# LionIRVT-Power.net
KiCad netlist of a schematic drawn in Altium Designer
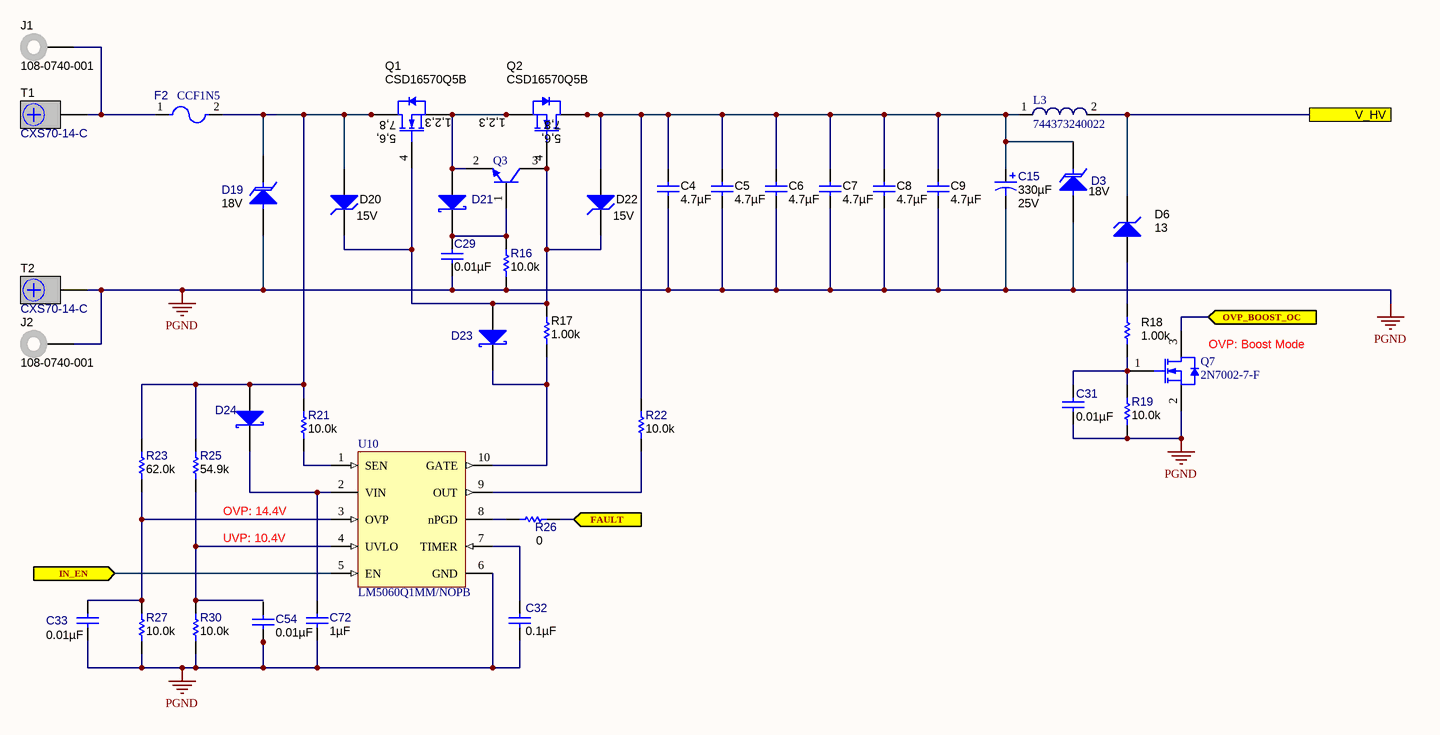
[diagram p0: LionIRVT-Power.SchDoc]

(export (version "E")
  (design (tool "Eeschema 10.0.6"))
  (components
    (comp (ref "C4")
      (value "C5750X7R2A475M230KA")
      (footprint "2220_280")
      (description "CAP, CERM, 4.7 µF, 100 V, +/- 20%, X7R, 2220")
      (fields
        (field (name "VALUEDISPLAYED") "4.7µF")
        (field (name "MANUFACTURER") "TDK")
        (field (name "PUBLISHER") "Texas Instruments")
      )
      (libsource (lib "Capacitor_Ceramic") (part "C5750X7R2A475M230KA"))
    )
    (comp (ref "C5")
      (value "C5750X7R2A475M230KA")
      (footprint "2220_280")
      (description "CAP, CERM, 4.7 µF, 100 V, +/- 20%, X7R, 2220")
      (fields
        (field (name "VALUEDISPLAYED") "4.7µF")
        (field (name "MANUFACTURER") "TDK")
        (field (name "PUBLISHER") "Texas Instruments")
      )
      (libsource (lib "Capacitor_Ceramic") (part "C5750X7R2A475M230KA"))
    )
    (comp (ref "C6")
      (value "C5750X7R2A475M230KA")
      (footprint "2220_280")
      (description "CAP, CERM, 4.7 µF, 100 V, +/- 20%, X7R, 2220")
      (fields
        (field (name "VALUEDISPLAYED") "4.7µF")
        (field (name "MANUFACTURER") "TDK")
        (field (name "PUBLISHER") "Texas Instruments")
      )
      (libsource (lib "Capacitor_Ceramic") (part "C5750X7R2A475M230KA"))
    )
    (comp (ref "C7")
      (value "C5750X7R2A475M230KA")
      (footprint "2220_280")
      (description "CAP, CERM, 4.7 µF, 100 V, +/- 20%, X7R, 2220")
      (fields
        (field (name "VALUEDISPLAYED") "4.7µF")
        (field (name "MANUFACTURER") "TDK")
        (field (name "PUBLISHER") "Texas Instruments")
      )
      (libsource (lib "Capacitor_Ceramic") (part "C5750X7R2A475M230KA"))
    )
    (comp (ref "C8")
      (value "C5750X7R2A475M230KA")
      (footprint "2220_280")
      (description "CAP, CERM, 4.7 µF, 100 V, +/- 20%, X7R, 2220")
      (fields
        (field (name "VALUEDISPLAYED") "4.7µF")
        (field (name "MANUFACTURER") "TDK")
        (field (name "PUBLISHER") "Texas Instruments")
      )
      (libsource (lib "Capacitor_Ceramic") (part "C5750X7R2A475M230KA"))
    )
    (comp (ref "C9")
      (value "C5750X7R2A475M230KA")
      (footprint "2220_280")
      (description "CAP, CERM, 4.7 µF, 100 V, +/- 20%, X7R, 2220")
      (fields
        (field (name "VALUEDISPLAYED") "4.7µF")
        (field (name "MANUFACTURER") "TDK")
        (field (name "PUBLISHER") "Texas Instruments")
      )
      (libsource (lib "Capacitor_Ceramic") (part "C5750X7R2A475M230KA"))
    )
    (comp (ref "C15")
      (value "25SVPF330M")
      (footprint "CAPSMT_62_F12")
      (fields
        (field (name "VALUEDISPLAYED") "330µF")
        (field (name "MANUFACTURER") "Panasonic")
        (field (name "VALUE2") "25V")
        (field (name "PUBLISHER") "Texas Instruments")
      )
      (libsource (lib "PMP40182") (part "25SVPF330M"))
    )
    (comp (ref "C29")
      (value "GRM1885C1H103JA01D")
      (footprint "0603C")
      (description "CAP, CERM, 0.01 µF, 50 V, +/- 5%, C0G/NP0, 0603")
      (fields
        (field (name "VALUEDISPLAYED") "0.01µF")
        (field (name "MANUFACTURER") "MuRata")
        (field (name "PUBLISHER") "Texas Instruments")
      )
      (libsource (lib "Capacitor_Ceramic") (part "GRM1885C1H103JA01D"))
    )
    (comp (ref "C31")
      (value "GRM1885C1H103JA01D")
      (footprint "0603C")
      (description "CAP, CERM, 0.01 µF, 50 V, +/- 5%, C0G/NP0, 0603")
      (fields
        (field (name "VALUEDISPLAYED") "0.01µF")
        (field (name "MANUFACTURER") "MuRata")
        (field (name "PUBLISHER") "Texas Instruments")
      )
      (libsource (lib "Capacitor_Ceramic") (part "GRM1885C1H103JA01D"))
    )
    (comp (ref "C32")
      (value "C0603C104J3RACTU")
      (footprint "0603C")
      (description "CAP, CERM, 0.1 µF, 25 V, +/- 5%, X7R, 0603")
      (fields
        (field (name "VALUEDISPLAYED") "0.1µF")
        (field (name "MANUFACTURER") "Kemet")
        (field (name "PUBLISHER") "Texas Instruments")
      )
      (libsource (lib "Capacitor_Ceramic") (part "C0603C104J3RACTU"))
    )
    (comp (ref "C33")
      (value "GRM1885C1H103JA01D")
      (footprint "0603C")
      (description "CAP, CERM, 0.01 µF, 50 V, +/- 5%, C0G/NP0, 0603")
      (fields
        (field (name "VALUEDISPLAYED") "0.01µF")
        (field (name "MANUFACTURER") "MuRata")
        (field (name "PUBLISHER") "Texas Instruments")
      )
      (libsource (lib "Capacitor_Ceramic") (part "GRM1885C1H103JA01D"))
    )
    (comp (ref "C54")
      (value "GRM1885C1H103JA01D")
      (footprint "0603C")
      (description "CAP, CERM, 0.01 µF, 50 V, +/- 5%, C0G/NP0, 0603")
      (fields
        (field (name "VALUEDISPLAYED") "0.01µF")
        (field (name "MANUFACTURER") "MuRata")
        (field (name "PUBLISHER") "Texas Instruments")
      )
      (libsource (lib "Capacitor_Ceramic") (part "GRM1885C1H103JA01D"))
    )
    (comp (ref "C72")
      (value "C0603C105K3RACTU")
      (footprint "0603C")
      (description "CAP, CERM, 1 µF, 25 V, +/- 10%, X7R, 0603")
      (fields
        (field (name "VALUEDISPLAYED") "1µF")
        (field (name "MANUFACTURER") "Kemet")
        (field (name "PUBLISHER") "Texas Instruments")
      )
      (libsource (lib "Capacitor_Ceramic") (part "C0603C105K3RACTU"))
    )
    (comp (ref "D3")
      (value "18V")
      (footprint "SMA")
      (description "Diode, TVS, Uni, 18 V, 29.2 Vc, SMA")
      (fields
        (field (name "PARTNUMBER") "SMAJ18A")
        (field (name "MANUFACTURER") "Littelfuse")
        (field (name "PUBLISHER") "Texas Instruments")
      )
      (libsource (lib "PMP40182") (part "SMAJ18A"))
    )
    (comp (ref "D6")
      (value "13")
      (footprint "sod-323")
      (description "Diode, Zener, 13V, 200mW, SOD-323")
      (fields
        (field (name "PARTNUMBER") "MMSZ5243BS-7-F")
        (field (name "MANUFACTURER") "Diodes Inc.")
        (field (name "PUBLISHER") "Texas Instruments")
      )
      (libsource (lib "PWR578A") (part "MMSZ5243BS-7-F"))
    )
    (comp (ref "D19")
      (value "18V")
      (footprint "SMA")
      (description "Diode, TVS, Uni, 18 V, 29.2 Vc, SMA")
      (fields
        (field (name "PARTNUMBER") "SMAJ18A")
        (field (name "MANUFACTURER") "Littelfuse")
        (field (name "PUBLISHER") "Texas Instruments")
      )
      (libsource (lib "ZenerDiodes") (part "SMAJ18A"))
    )
    (comp (ref "D20")
      (value "15V")
      (footprint "sod-323")
      (description "Diode, Zener, 15 V, 200 mW, SOD-323")
      (fields
        (field (name "PARTNUMBER") "MMSZ5245BS-7-F")
        (field (name "MANUFACTURER") "Diodes Inc.")
        (field (name "SYMBOLCREATOR") "a0412235")
        (field (name "PUBLISHER") "Texas Instruments")
      )
      (libsource (lib "ZenerDiodes") (part "MMSZ5245BS-7-F"))
    )
    (comp (ref "D21")
      (value "NSR0240V2T1G")
      (footprint "SOD-523")
      (description "Diode, Schottky, 40V, 0.25A, SOD-523")
      (fields (field (name "MANUFACTURER") "ON Semiconductor") (field (name "PUBLISHER") "Texas Instruments"))
      (libsource (lib "Diode") (part "NSR0240V2T1G"))
    )
    (comp (ref "D22")
      (value "15V")
      (footprint "sod-323")
      (description "Diode, Zener, 15 V, 200 mW, SOD-323")
      (fields
        (field (name "PARTNUMBER") "MMSZ5245BS-7-F")
        (field (name "MANUFACTURER") "Diodes Inc.")
        (field (name "SYMBOLCREATOR") "a0412235")
        (field (name "PUBLISHER") "Texas Instruments")
      )
      (libsource (lib "ZenerDiodes") (part "MMSZ5245BS-7-F"))
    )
    (comp (ref "D23")
      (value "NSR0240V2T1G")
      (footprint "SOD-523")
      (description "Diode, Schottky, 40V, 0.25A, SOD-523")
      (fields (field (name "MANUFACTURER") "ON Semiconductor") (field (name "PUBLISHER") "Texas Instruments"))
      (libsource (lib "Diode") (part "NSR0240V2T1G"))
    )
    (comp (ref "D24")
      (value "NSR0240V2T1G")
      (footprint "SOD-523")
      (description "Diode, Schottky, 40V, 0.25A, SOD-523")
      (fields (field (name "MANUFACTURER") "ON Semiconductor") (field (name "PUBLISHER") "Texas Instruments"))
      (libsource (lib "Diode") (part "NSR0240V2T1G"))
    )
    (comp (ref "F2")
      (value "CCF1N5")
      (footprint "FUSE_CCF")
      (description "Fuse, Fast Acting, 50VDC, 20A")
      (fields (field (name "MANUFACTURER") "Koanet"))
      (libsource (lib "PADSlegacy_Passive") (part "FUSE_CCF1N_SERIES"))
    )
    (comp (ref "J1")
      (value "108-0740-001")
      (footprint "Johnson_108-0740-001")
      (description "Standard Banana Jack, Uninsulated, 15A")
      (fields
        (field (name "MANUFACTURER") "Emerson Network Power")
        (field (name "SYMBOLCREATOR") "a0412235")
        (field (name "PUBLISHER") "Texas Instruments")
      )
      (libsource (lib "Connectors_Other") (part "108-0740-001"))
    )
    (comp (ref "J2")
      (value "108-0740-001")
      (footprint "Johnson_108-0740-001")
      (description "Standard Banana Jack, Uninsulated, 15A")
      (fields
        (field (name "MANUFACTURER") "Emerson Network Power")
        (field (name "SYMBOLCREATOR") "a0412235")
        (field (name "PUBLISHER") "Texas Instruments")
      )
      (libsource (lib "Connectors_Other") (part "108-0740-001"))
    )
    (comp (ref "L3")
      (value "744373240022")
      (footprint "WE-LHMI 4020")
      (description "SMD Power Inductor WE-LHMI, L=0.22 µH")
      (fields (field (name "MANUFACTURER") "Wuerth Elektronik"))
      (libsource (lib "Altium Content Vault") (part "WE-IND-INDUCTOR-2"))
    )
    (comp (ref "Q1")
      (value "CSD16570Q5B")
      (footprint "DNK8")
      (description "25V, N ch NexFET MOSFET™, single SON5x6, 0.82mOhm")
      (fields
        (field (name "MANUFACTURER") "Texas Instruments")
        (field (name "MANUFACTURER PART NUMBER") "CSD16570Q5BT")
      )
      (libsource (lib "PWR578A") (part "CSD16570Q5B"))
    )
    (comp (ref "Q2")
      (value "CSD16570Q5B")
      (footprint "DNK8")
      (description "25V, N ch NexFET MOSFET™, single SON5x6, 0.82mOhm")
      (fields
        (field (name "MANUFACTURER") "Texas Instruments")
        (field (name "MANUFACTURER PART NUMBER") "CSD16570Q5BT")
      )
      (libsource (lib "PWR578A") (part "CSD16570Q5B"))
    )
    (comp (ref "Q3")
      (value "MMBT2222ALT1G")
      (footprint "ONSC-SOT-23-3-318-08_V")
      (description "General Purpose Transistor, NPN Silicon, 3-Pin SOT-23, Pb-Free, Tape and Reel")
      (fields (field (name "MANUFACTURER") "On Semiconductor"))
      (libsource (lib "Altium Content Vault") (part "ONSC-NPN-B1E2C3-3"))
    )
    (comp (ref "Q7")
      (value "2N7002-7-F")
      (footprint "DIOD-SOT23-3_V")
      (fields (field (name "MANUFACTURER") "DiodesIncorporated"))
      (libsource (lib "Altium Content Vault") (part "NEMOS-GSD-3"))
    )
    (comp (ref "R16")
      (value "RC0603FR-0710KL")
      (footprint "0603R")
      (description "RES, 10.0 k, 1%, 0.1 W, 0603")
      (fields
        (field (name "VALUEDISPLAYED") "10.0k")
        (field (name "MANUFACTURER") "Yageo America")
        (field (name "PUBLISHER") "Texas Instruments")
      )
      (libsource (lib "Resistor_0603") (part "RC0603FR-0710KL"))
    )
    (comp (ref "R17")
      (value "Resistor")
      (footprint "0603R")
      (description "RES, 1.00 k, 1%, 0.1 W, AEC-Q200 Grade 0, 0603")
      (fields
        (field (name "PARTNUMBER") "CRCW06031K00FKEA")
        (field (name "MANUFACTURER") "Vishay-Dale")
        (field (name "VALUEDISPLAYED") "1.00k")
      )
      (libsource (lib "PMP40182") (part "CMP-0022109-5"))
    )
    (comp (ref "R18")
      (value "Resistor")
      (footprint "0603R")
      (description "RES, 1.00 k, 1%, 0.1 W, AEC-Q200 Grade 0, 0603")
      (fields
        (field (name "PARTNUMBER") "CRCW06031K00FKEA")
        (field (name "MANUFACTURER") "Vishay-Dale")
        (field (name "VALUEDISPLAYED") "1.00k")
      )
      (libsource (lib "PMP40182") (part "CMP-0022109-5"))
    )
    (comp (ref "R19")
      (value "RC0603FR-0710KL")
      (footprint "0603R")
      (description "RES, 10.0 k, 1%, 0.1 W, 0603")
      (fields
        (field (name "VALUEDISPLAYED") "10.0k")
        (field (name "MANUFACTURER") "Yageo America")
        (field (name "PUBLISHER") "Texas Instruments")
      )
      (libsource (lib "Resistor_0603") (part "RC0603FR-0710KL"))
    )
    (comp (ref "R21")
      (value "RC0603FR-0710KL")
      (footprint "0603R")
      (description "RES, 10.0 k, 1%, 0.1 W, 0603")
      (fields
        (field (name "VALUEDISPLAYED") "10.0k")
        (field (name "MANUFACTURER") "Yageo America")
        (field (name "PUBLISHER") "Texas Instruments")
      )
      (libsource (lib "Resistor_0603") (part "RC0603FR-0710KL"))
    )
    (comp (ref "R22")
      (value "RC0603FR-0710KL")
      (footprint "0603R")
      (description "RES, 10.0 k, 1%, 0.1 W, 0603")
      (fields
        (field (name "VALUEDISPLAYED") "10.0k")
        (field (name "MANUFACTURER") "Yageo America")
        (field (name "PUBLISHER") "Texas Instruments")
      )
      (libsource (lib "Resistor_0603") (part "RC0603FR-0710KL"))
    )
    (comp (ref "R23")
      (value "RC0603FR-0762KL")
      (footprint "0603R")
      (description "RES, 62.0 k, 1%, 0.1 W, 0603")
      (fields
        (field (name "VALUEDISPLAYED") "62.0k")
        (field (name "MANUFACTURER") "Yageo America")
        (field (name "PUBLISHER") "Texas Instruments")
      )
      (libsource (lib "Resistor_0603") (part "RC0603FR-0762KL"))
    )
    (comp (ref "R25")
      (value "RC0603FR-0754K9L")
      (footprint "0603R")
      (description "RES, 54.9 k, 1%, 0.1 W, 0603")
      (fields
        (field (name "VALUEDISPLAYED") "54.9k")
        (field (name "MANUFACTURER") "Yageo America")
        (field (name "PUBLISHER") "Texas Instruments")
      )
      (libsource (lib "Resistor_0603") (part "RC0603FR-0754K9L"))
    )
    (comp (ref "R26")
      (value "RC0603JR-070RL")
      (footprint "0603R")
      (description "RES, 0, 5%, 0.1 W, 0603")
      (fields
        (field (name "VALUEDISPLAYED") "0")
        (field (name "MANUFACTURER") "Yageo America")
        (field (name "PUBLISHER") "Texas Instruments")
      )
      (libsource (lib "Resistor_0603") (part "RC0603JR-070RL"))
    )
    (comp (ref "R27")
      (value "RC0603FR-0710KL")
      (footprint "0603R")
      (description "RES, 10.0 k, 1%, 0.1 W, 0603")
      (fields
        (field (name "VALUEDISPLAYED") "10.0k")
        (field (name "MANUFACTURER") "Yageo America")
        (field (name "PUBLISHER") "Texas Instruments")
      )
      (libsource (lib "Resistor_0603") (part "RC0603FR-0710KL"))
    )
    (comp (ref "R30")
      (value "RC0603FR-0710KL")
      (footprint "0603R")
      (description "RES, 10.0 k, 1%, 0.1 W, 0603")
      (fields
        (field (name "VALUEDISPLAYED") "10.0k")
        (field (name "MANUFACTURER") "Yageo America")
        (field (name "PUBLISHER") "Texas Instruments")
      )
      (libsource (lib "Resistor_0603") (part "RC0603FR-0710KL"))
    )
    (comp (ref "T1")
      (value "CXS70-14-C")
      (footprint "Panduit_CXS70-14-C")
      (description "Terminal 70A Lug")
      (fields
        (field (name "MANUFACTURER") "Panduit")
        (field (name "SYMBOLCREATOR") "crossc")
        (field (name "PUBLISHER") "Texas Instruments")
      )
      (libsource (lib "Connectors_Other") (part "CXS70-14-C"))
    )
    (comp (ref "T2")
      (value "CXS70-14-C")
      (footprint "Panduit_CXS70-14-C")
      (description "Terminal 70A Lug")
      (fields
        (field (name "MANUFACTURER") "Panduit")
        (field (name "SYMBOLCREATOR") "crossc")
        (field (name "PUBLISHER") "Texas Instruments")
      )
      (libsource (lib "Connectors_Other") (part "CXS70-14-C"))
    )
    (comp (ref "U10")
      (value "LM5060Q1MM/NOPB")
      (footprint "DGS0010A_N")
      (description "High-Side Protection Controller with Low Quiescent Current, 10-pin MSOP, Pb-Free")
      (fields (field (name "MANUFACTURER") "Texas Instruments"))
      (libsource (lib "Altium Content Vault") (part "PM-CNTL-LM5060MM-10"))
    )
  )
  (nets
    (net (code "1") (name "/FAULT") (class "Default")
      (node (ref "R26") (pin "1") (pinfunction "1_1") (pintype "passive"))
    )
    (net (code "2") (name "/IN_EN") (class "Default")
      (node (ref "U10") (pin "5") (pinfunction "EN_5") (pintype "input"))
    )
    (net (code "3") (name "/OVP_BOOST_OC") (class "Default")
      (node (ref "Q7") (pin "3") (pinfunction "D_3") (pintype "passive"))
    )
    (net (code "4") (name "/V_HV") (class "Default")
      (node (ref "D6") (pin "1") (pinfunction "K_1") (pintype "passive"))
      (node (ref "L3") (pin "2") (pinfunction "2_2") (pintype "passive"))
    )
    (net (code "5") (name "Net-(C15-+)") (class "Default")
      (node (ref "C15") (pin "1") (pinfunction "+_1") (pintype "passive"))
      (node (ref "C4") (pin "1") (pinfunction "1_1") (pintype "passive"))
      (node (ref "C5") (pin "1") (pinfunction "1_1") (pintype "passive"))
      (node (ref "C6") (pin "1") (pinfunction "1_1") (pintype "passive"))
      (node (ref "C7") (pin "1") (pinfunction "1_1") (pintype "passive"))
      (node (ref "C8") (pin "1") (pinfunction "1_1") (pintype "passive"))
      (node (ref "C9") (pin "1") (pinfunction "1_1") (pintype "passive"))
      (node (ref "D22") (pin "2") (pinfunction "A_2") (pintype "passive"))
      (node (ref "D3") (pin "1") (pinfunction "K_1") (pintype "passive"))
      (node (ref "L3") (pin "1") (pinfunction "1_1") (pintype "passive"))
      (node (ref "Q2") (pin "5") (pinfunction "D_5") (pintype "passive"))
      (node (ref "Q2") (pin "6") (pinfunction "D_6") (pintype "passive"))
      (node (ref "Q2") (pin "7") (pinfunction "D_7") (pintype "passive"))
      (node (ref "Q2") (pin "8") (pinfunction "D_8") (pintype "passive"))
      (node (ref "R22") (pin "1") (pinfunction "1_1") (pintype "passive"))
    )
    (net (code "6") (name "Net-(D6-A)") (class "Default")
      (node (ref "D6") (pin "2") (pinfunction "A_2") (pintype "passive"))
      (node (ref "R18") (pin "2") (pinfunction "2_2") (pintype "passive"))
    )
    (net (code "7") (name "Net-(D19-K)") (class "Default")
      (node (ref "D19") (pin "1") (pinfunction "K_1") (pintype "passive"))
      (node (ref "D20") (pin "2") (pinfunction "A_2") (pintype "passive"))
      (node (ref "D24") (pin "2") (pinfunction "A_2") (pintype "passive"))
      (node (ref "F2") (pin "2") (pintype "passive"))
      (node (ref "Q1") (pin "5") (pinfunction "D_5") (pintype "passive"))
      (node (ref "Q1") (pin "6") (pinfunction "D_6") (pintype "passive"))
      (node (ref "Q1") (pin "7") (pinfunction "D_7") (pintype "passive"))
      (node (ref "Q1") (pin "8") (pinfunction "D_8") (pintype "passive"))
      (node (ref "R21") (pin "1") (pinfunction "1_1") (pintype "passive"))
      (node (ref "R23") (pin "2") (pinfunction "2_2") (pintype "passive"))
      (node (ref "R25") (pin "2") (pinfunction "2_2") (pintype "passive"))
    )
    (net (code "8") (name "Net-(D20-K)") (class "Default")
      (node (ref "D20") (pin "1") (pinfunction "K_1") (pintype "passive"))
      (node (ref "D22") (pin "1") (pinfunction "K_1") (pintype "passive"))
      (node (ref "D23") (pin "2") (pinfunction "A_2") (pintype "passive"))
      (node (ref "Q1") (pin "4") (pinfunction "G_4") (pintype "passive"))
      (node (ref "Q2") (pin "4") (pinfunction "G_4") (pintype "passive"))
      (node (ref "Q3") (pin "3") (pinfunction "C_3") (pintype "passive"))
      (node (ref "R17") (pin "2") (pinfunction "2_2") (pintype "passive"))
    )
    (net (code "9") (name "Net-(D21-A)") (class "Default")
      (node (ref "D21") (pin "2") (pinfunction "A_2") (pintype "passive"))
      (node (ref "Q1") (pin "1") (pinfunction "S_1") (pintype "passive"))
      (node (ref "Q1") (pin "2") (pinfunction "S_2") (pintype "passive"))
      (node (ref "Q1") (pin "3") (pinfunction "S_3") (pintype "passive"))
      (node (ref "Q2") (pin "1") (pinfunction "S_1") (pintype "passive"))
      (node (ref "Q2") (pin "2") (pinfunction "S_2") (pintype "passive"))
      (node (ref "Q2") (pin "3") (pinfunction "S_3") (pintype "passive"))
      (node (ref "Q3") (pin "2") (pinfunction "E_2") (pintype "passive"))
    )
    (net (code "10") (name "Net-(D21-K)") (class "Default")
      (node (ref "C29") (pin "1") (pinfunction "1_1") (pintype "passive"))
      (node (ref "D21") (pin "1") (pinfunction "K_1") (pintype "passive"))
      (node (ref "Q3") (pin "1") (pinfunction "B_1") (pintype "passive"))
      (node (ref "R16") (pin "1") (pinfunction "1_1") (pintype "passive"))
    )
    (net (code "11") (name "Net-(D23-K)") (class "Default")
      (node (ref "D23") (pin "1") (pinfunction "K_1") (pintype "passive"))
      (node (ref "R17") (pin "1") (pinfunction "1_1") (pintype "passive"))
      (node (ref "U10") (pin "10") (pinfunction "GATE_10") (pintype "output"))
    )
    (net (code "12") (name "Net-(D24-K)") (class "Default")
      (node (ref "C72") (pin "1") (pinfunction "1_1") (pintype "passive"))
      (node (ref "D24") (pin "1") (pinfunction "K_1") (pintype "passive"))
      (node (ref "U10") (pin "2") (pinfunction "VIN_2") (pintype "power_in"))
    )
    (net (code "13") (name "Net-(F2-Pad1)") (class "Default")
      (node (ref "F2") (pin "1") (pintype "passive"))
      (node (ref "J1") (pin "1") (pinfunction "1_1") (pintype "passive"))
      (node (ref "T1") (pin "1") (pinfunction "1_1") (pintype "passive"))
    )
    (net (code "14") (name "Net-(Q7-G)") (class "Default")
      (node (ref "C31") (pin "2") (pinfunction "2_2") (pintype "passive"))
      (node (ref "Q7") (pin "1") (pinfunction "G_1") (pintype "passive"))
      (node (ref "R18") (pin "1") (pinfunction "1_1") (pintype "passive"))
      (node (ref "R19") (pin "1") (pinfunction "1_1") (pintype "passive"))
    )
    (net (code "15") (name "Net-(U10-OUT)") (class "Default")
      (node (ref "R22") (pin "2") (pinfunction "2_2") (pintype "passive"))
      (node (ref "U10") (pin "9") (pinfunction "OUT_9") (pintype "output"))
    )
    (net (code "16") (name "Net-(U10-OVP)") (class "Default")
      (node (ref "C33") (pin "2") (pinfunction "2_2") (pintype "passive"))
      (node (ref "R23") (pin "1") (pinfunction "1_1") (pintype "passive"))
      (node (ref "R27") (pin "1") (pinfunction "1_1") (pintype "passive"))
      (node (ref "U10") (pin "3") (pinfunction "OVP_3") (pintype "input"))
    )
    (net (code "17") (name "Net-(U10-SEN)") (class "Default")
      (node (ref "R21") (pin "2") (pinfunction "2_2") (pintype "passive"))
      (node (ref "U10") (pin "1") (pinfunction "SEN_1") (pintype "input"))
    )
    (net (code "18") (name "Net-(U10-TIMER)") (class "Default")
      (node (ref "C32") (pin "2") (pinfunction "2_2") (pintype "passive"))
      (node (ref "U10") (pin "7") (pinfunction "TIMER_7") (pintype "input"))
    )
    (net (code "19") (name "Net-(U10-UVLO)") (class "Default")
      (node (ref "R25") (pin "1") (pinfunction "1_1") (pintype "passive"))
      (node (ref "R30") (pin "1") (pinfunction "1_1") (pintype "passive"))
      (node (ref "U10") (pin "4") (pinfunction "UVLO_4") (pintype "input"))
    )
    (net (code "20") (name "Net-(U10-nPGD)") (class "Default")
      (node (ref "R26") (pin "2") (pinfunction "2_2") (pintype "passive"))
      (node (ref "U10") (pin "8") (pinfunction "nPGD_8") (pintype "open_collector"))
    )
    (net (code "21") (name "PGND") (class "Default")
      (node (ref "C15") (pin "2") (pinfunction "-_2") (pintype "passive"))
      (node (ref "C29") (pin "2") (pinfunction "2_2") (pintype "passive"))
      (node (ref "C31") (pin "1") (pinfunction "1_1") (pintype "passive"))
      (node (ref "C32") (pin "1") (pinfunction "1_1") (pintype "passive"))
      (node (ref "C33") (pin "1") (pinfunction "1_1") (pintype "passive"))
      (node (ref "C4") (pin "2") (pinfunction "2_2") (pintype "passive"))
      (node (ref "C5") (pin "2") (pinfunction "2_2") (pintype "passive"))
      (node (ref "C54") (pin "1") (pinfunction "1_1") (pintype "passive"))
      (node (ref "C6") (pin "2") (pinfunction "2_2") (pintype "passive"))
      (node (ref "C7") (pin "2") (pinfunction "2_2") (pintype "passive"))
      (node (ref "C72") (pin "2") (pinfunction "2_2") (pintype "passive"))
      (node (ref "C8") (pin "2") (pinfunction "2_2") (pintype "passive"))
      (node (ref "C9") (pin "2") (pinfunction "2_2") (pintype "passive"))
      (node (ref "D19") (pin "2") (pinfunction "A_2") (pintype "passive"))
      (node (ref "D3") (pin "2") (pinfunction "A_2") (pintype "passive"))
      (node (ref "J2") (pin "1") (pinfunction "1_1") (pintype "passive"))
      (node (ref "Q7") (pin "2") (pinfunction "S_2") (pintype "passive"))
      (node (ref "R16") (pin "2") (pinfunction "2_2") (pintype "passive"))
      (node (ref "R19") (pin "2") (pinfunction "2_2") (pintype "passive"))
      (node (ref "R27") (pin "2") (pinfunction "2_2") (pintype "passive"))
      (node (ref "R30") (pin "2") (pinfunction "2_2") (pintype "passive"))
      (node (ref "T2") (pin "1") (pinfunction "1_1") (pintype "passive"))
      (node (ref "U10") (pin "6") (pinfunction "GND_6") (pintype "power_in"))
    )
    (net (code "22") (name "unconnected-(C54-Pad2)") (class "Default")
      (node (ref "C54") (pin "2") (pinfunction "2_2") (pintype "passive"))
    )
  )
)
